# R205B.net
KiCad netlist of a schematic drawn in EAGLE
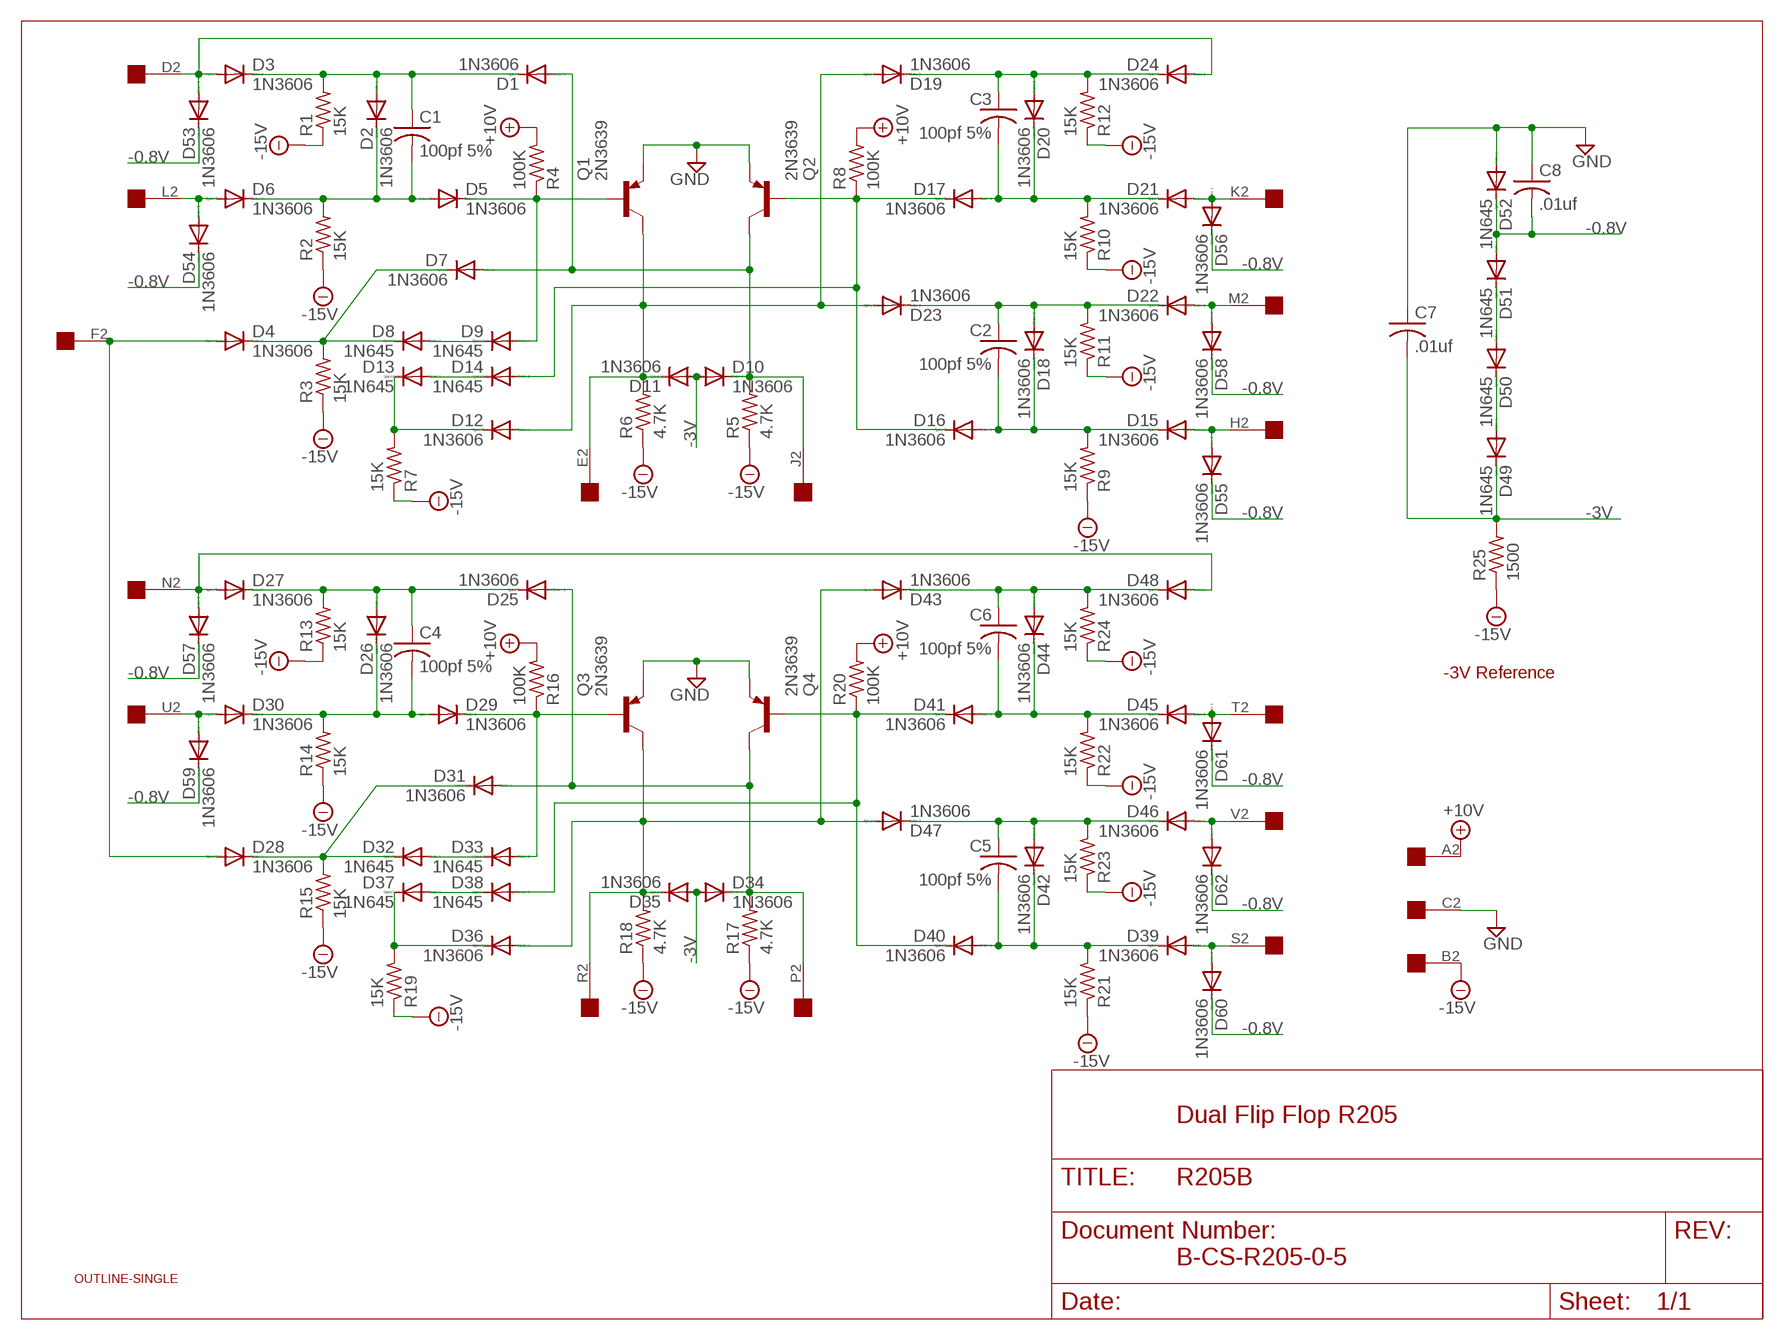
[diagram p0: schematic, sheet 1]

(export (version "E")
  (design (tool "Eeschema 10.0.6"))
  (components
    (comp (ref "C1")
      (value "100pf 5%")
      (footprint "eagle-import:C050-025X075")
      (libsource (lib "eagle-import") (part "C-US050-025X075"))
    )
    (comp (ref "C2")
      (value "100pf 5%")
      (footprint "eagle-import:C050-025X075")
      (libsource (lib "eagle-import") (part "C-US050-025X075"))
    )
    (comp (ref "C3")
      (value "100pf 5%")
      (footprint "eagle-import:C050-025X075")
      (libsource (lib "eagle-import") (part "C-US050-025X075"))
    )
    (comp (ref "C4")
      (value "100pf 5%")
      (footprint "eagle-import:C050-025X075")
      (libsource (lib "eagle-import") (part "C-US050-025X075"))
    )
    (comp (ref "C5")
      (value "100pf 5%")
      (footprint "eagle-import:C050-025X075")
      (libsource (lib "eagle-import") (part "C-US050-025X075"))
    )
    (comp (ref "C6")
      (value "100pf 5%")
      (footprint "eagle-import:C050-025X075")
      (libsource (lib "eagle-import") (part "C-US050-025X075"))
    )
    (comp (ref "C7")
      (value ".01uf")
      (footprint "eagle-import:C050-025X075")
      (libsource (lib "eagle-import") (part "C-US050-025X075"))
    )
    (comp (ref "C8")
      (value ".01uf")
      (footprint "eagle-import:C050-025X075")
      (libsource (lib "eagle-import") (part "C-US050-025X075"))
    )
    (comp (ref "D1")
      (value "1N3606")
      (footprint "eagle-import:DO35-10")
      (libsource (lib "eagle-import") (part "1N4148DO35-10"))
    )
    (comp (ref "D2")
      (value "1N3606")
      (footprint "eagle-import:DO35-10")
      (libsource (lib "eagle-import") (part "1N4148DO35-10"))
    )
    (comp (ref "D3")
      (value "1N3606")
      (footprint "eagle-import:DO35-10")
      (libsource (lib "eagle-import") (part "1N4148DO35-10"))
    )
    (comp (ref "D4")
      (value "1N3606")
      (footprint "eagle-import:DO35-10")
      (libsource (lib "eagle-import") (part "1N4148DO35-10"))
    )
    (comp (ref "D5")
      (value "1N3606")
      (footprint "eagle-import:DO35-10")
      (libsource (lib "eagle-import") (part "1N4148DO35-10"))
    )
    (comp (ref "D6")
      (value "1N3606")
      (footprint "eagle-import:DO35-10")
      (libsource (lib "eagle-import") (part "1N4148DO35-10"))
    )
    (comp (ref "D7")
      (value "1N3606")
      (footprint "eagle-import:DO35-10")
      (libsource (lib "eagle-import") (part "1N4148DO35-10"))
    )
    (comp (ref "D8")
      (value "1N645")
      (footprint "eagle-import:DO35-10")
      (libsource (lib "eagle-import") (part "1N4148DO35-10"))
    )
    (comp (ref "D9")
      (value "1N645")
      (footprint "eagle-import:DO35-10")
      (libsource (lib "eagle-import") (part "1N4148DO35-10"))
    )
    (comp (ref "D10")
      (value "1N3606")
      (footprint "eagle-import:DO35-10")
      (libsource (lib "eagle-import") (part "1N4148DO35-10"))
    )
    (comp (ref "D11")
      (value "1N3606")
      (footprint "eagle-import:DO35-10")
      (libsource (lib "eagle-import") (part "1N4148DO35-10"))
    )
    (comp (ref "D12")
      (value "1N3606")
      (footprint "eagle-import:DO35-10")
      (libsource (lib "eagle-import") (part "1N4148DO35-10"))
    )
    (comp (ref "D13")
      (value "1N645")
      (footprint "eagle-import:DO35-10")
      (libsource (lib "eagle-import") (part "1N4148DO35-10"))
    )
    (comp (ref "D14")
      (value "1N645")
      (footprint "eagle-import:DO35-10")
      (libsource (lib "eagle-import") (part "1N4148DO35-10"))
    )
    (comp (ref "D15")
      (value "1N3606")
      (footprint "eagle-import:DO35-10")
      (libsource (lib "eagle-import") (part "1N4148DO35-10"))
    )
    (comp (ref "D16")
      (value "1N3606")
      (footprint "eagle-import:DO35-10")
      (libsource (lib "eagle-import") (part "1N4148DO35-10"))
    )
    (comp (ref "D17")
      (value "1N3606")
      (footprint "eagle-import:DO35-10")
      (libsource (lib "eagle-import") (part "1N4148DO35-10"))
    )
    (comp (ref "D18")
      (value "1N3606")
      (footprint "eagle-import:DO35-10")
      (libsource (lib "eagle-import") (part "1N4148DO35-10"))
    )
    (comp (ref "D19")
      (value "1N3606")
      (footprint "eagle-import:DO35-10")
      (libsource (lib "eagle-import") (part "1N4148DO35-10"))
    )
    (comp (ref "D20")
      (value "1N3606")
      (footprint "eagle-import:DO35-10")
      (libsource (lib "eagle-import") (part "1N4148DO35-10"))
    )
    (comp (ref "D21")
      (value "1N3606")
      (footprint "eagle-import:DO35-10")
      (libsource (lib "eagle-import") (part "1N4148DO35-10"))
    )
    (comp (ref "D22")
      (value "1N3606")
      (footprint "eagle-import:DO35-10")
      (libsource (lib "eagle-import") (part "1N4148DO35-10"))
    )
    (comp (ref "D23")
      (value "1N3606")
      (footprint "eagle-import:DO35-10")
      (libsource (lib "eagle-import") (part "1N4148DO35-10"))
    )
    (comp (ref "D24")
      (value "1N3606")
      (footprint "eagle-import:DO35-10")
      (libsource (lib "eagle-import") (part "1N4148DO35-10"))
    )
    (comp (ref "D25")
      (value "1N3606")
      (footprint "eagle-import:DO35-10")
      (libsource (lib "eagle-import") (part "1N4148DO35-10"))
    )
    (comp (ref "D26")
      (value "1N3606")
      (footprint "eagle-import:DO35-10")
      (libsource (lib "eagle-import") (part "1N4148DO35-10"))
    )
    (comp (ref "D27")
      (value "1N3606")
      (footprint "eagle-import:DO35-10")
      (libsource (lib "eagle-import") (part "1N4148DO35-10"))
    )
    (comp (ref "D28")
      (value "1N3606")
      (footprint "eagle-import:DO35-10")
      (libsource (lib "eagle-import") (part "1N4148DO35-10"))
    )
    (comp (ref "D29")
      (value "1N3606")
      (footprint "eagle-import:DO35-10")
      (libsource (lib "eagle-import") (part "1N4148DO35-10"))
    )
    (comp (ref "D30")
      (value "1N3606")
      (footprint "eagle-import:DO35-10")
      (libsource (lib "eagle-import") (part "1N4148DO35-10"))
    )
    (comp (ref "D31")
      (value "1N3606")
      (footprint "eagle-import:DO35-10")
      (libsource (lib "eagle-import") (part "1N4148DO35-10"))
    )
    (comp (ref "D32")
      (value "1N645")
      (footprint "eagle-import:DO35-10")
      (libsource (lib "eagle-import") (part "1N4148DO35-10"))
    )
    (comp (ref "D33")
      (value "1N645")
      (footprint "eagle-import:DO35-10")
      (libsource (lib "eagle-import") (part "1N4148DO35-10"))
    )
    (comp (ref "D34")
      (value "1N3606")
      (footprint "eagle-import:DO35-10")
      (libsource (lib "eagle-import") (part "1N4148DO35-10"))
    )
    (comp (ref "D35")
      (value "1N3606")
      (footprint "eagle-import:DO35-10")
      (libsource (lib "eagle-import") (part "1N4148DO35-10"))
    )
    (comp (ref "D36")
      (value "1N3606")
      (footprint "eagle-import:DO35-10")
      (libsource (lib "eagle-import") (part "1N4148DO35-10"))
    )
    (comp (ref "D37")
      (value "1N645")
      (footprint "eagle-import:DO35-10")
      (libsource (lib "eagle-import") (part "1N4148DO35-10"))
    )
    (comp (ref "D38")
      (value "1N645")
      (footprint "eagle-import:DO35-10")
      (libsource (lib "eagle-import") (part "1N4148DO35-10"))
    )
    (comp (ref "D39")
      (value "1N3606")
      (footprint "eagle-import:DO35-10")
      (libsource (lib "eagle-import") (part "1N4148DO35-10"))
    )
    (comp (ref "D40")
      (value "1N3606")
      (footprint "eagle-import:DO35-10")
      (libsource (lib "eagle-import") (part "1N4148DO35-10"))
    )
    (comp (ref "D41")
      (value "1N3606")
      (footprint "eagle-import:DO35-10")
      (libsource (lib "eagle-import") (part "1N4148DO35-10"))
    )
    (comp (ref "D42")
      (value "1N3606")
      (footprint "eagle-import:DO35-10")
      (libsource (lib "eagle-import") (part "1N4148DO35-10"))
    )
    (comp (ref "D43")
      (value "1N3606")
      (footprint "eagle-import:DO35-10")
      (libsource (lib "eagle-import") (part "1N4148DO35-10"))
    )
    (comp (ref "D44")
      (value "1N3606")
      (footprint "eagle-import:DO35-10")
      (libsource (lib "eagle-import") (part "1N4148DO35-10"))
    )
    (comp (ref "D45")
      (value "1N3606")
      (footprint "eagle-import:DO35-10")
      (libsource (lib "eagle-import") (part "1N4148DO35-10"))
    )
    (comp (ref "D46")
      (value "1N3606")
      (footprint "eagle-import:DO35-10")
      (libsource (lib "eagle-import") (part "1N4148DO35-10"))
    )
    (comp (ref "D47")
      (value "1N3606")
      (footprint "eagle-import:DO35-10")
      (libsource (lib "eagle-import") (part "1N4148DO35-10"))
    )
    (comp (ref "D48")
      (value "1N3606")
      (footprint "eagle-import:DO35-10")
      (libsource (lib "eagle-import") (part "1N4148DO35-10"))
    )
    (comp (ref "D49")
      (value "1N645")
      (footprint "eagle-import:DO35-10")
      (libsource (lib "eagle-import") (part "1N4148DO35-10"))
    )
    (comp (ref "D50")
      (value "1N645")
      (footprint "eagle-import:DO35-10")
      (libsource (lib "eagle-import") (part "1N4148DO35-10"))
    )
    (comp (ref "D51")
      (value "1N645")
      (footprint "eagle-import:DO35-10")
      (libsource (lib "eagle-import") (part "1N4148DO35-10"))
    )
    (comp (ref "D52")
      (value "1N645")
      (footprint "eagle-import:DO35-10")
      (libsource (lib "eagle-import") (part "1N4148DO35-10"))
    )
    (comp (ref "D53")
      (value "1N3606")
      (footprint "eagle-import:DO35-10")
      (libsource (lib "eagle-import") (part "1N4148DO35-10"))
    )
    (comp (ref "D54")
      (value "1N3606")
      (footprint "eagle-import:DO35-10")
      (libsource (lib "eagle-import") (part "1N4148DO35-10"))
    )
    (comp (ref "D55")
      (value "1N3606")
      (footprint "eagle-import:DO35-10")
      (libsource (lib "eagle-import") (part "1N4148DO35-10"))
    )
    (comp (ref "D56")
      (value "1N3606")
      (footprint "eagle-import:DO35-10")
      (libsource (lib "eagle-import") (part "1N4148DO35-10"))
    )
    (comp (ref "D57")
      (value "1N3606")
      (footprint "eagle-import:DO35-10")
      (libsource (lib "eagle-import") (part "1N4148DO35-10"))
    )
    (comp (ref "D58")
      (value "1N3606")
      (footprint "eagle-import:DO35-10")
      (libsource (lib "eagle-import") (part "1N4148DO35-10"))
    )
    (comp (ref "D59")
      (value "1N3606")
      (footprint "eagle-import:DO35-10")
      (libsource (lib "eagle-import") (part "1N4148DO35-10"))
    )
    (comp (ref "D60")
      (value "1N3606")
      (footprint "eagle-import:DO35-10")
      (libsource (lib "eagle-import") (part "1N4148DO35-10"))
    )
    (comp (ref "D61")
      (value "1N3606")
      (footprint "eagle-import:DO35-10")
      (libsource (lib "eagle-import") (part "1N4148DO35-10"))
    )
    (comp (ref "D62")
      (value "1N3606")
      (footprint "eagle-import:DO35-10")
      (libsource (lib "eagle-import") (part "1N4148DO35-10"))
    )
    (comp (ref "Q1")
      (value "2N3639")
      (footprint "eagle-import:TO39")
      (libsource (lib "eagle-import") (part "2N3637"))
    )
    (comp (ref "Q2")
      (value "2N3639")
      (footprint "eagle-import:TO39")
      (libsource (lib "eagle-import") (part "2N3637"))
    )
    (comp (ref "Q3")
      (value "2N3639")
      (footprint "eagle-import:TO39")
      (libsource (lib "eagle-import") (part "2N3637"))
    )
    (comp (ref "Q4")
      (value "2N3639")
      (footprint "eagle-import:TO39")
      (libsource (lib "eagle-import") (part "2N3637"))
    )
    (comp (ref "R1")
      (value "15K")
      (footprint "eagle-import:0207_10")
      (libsource (lib "eagle-import") (part "R-US_0207/10"))
    )
    (comp (ref "R2")
      (value "15K")
      (footprint "eagle-import:0207_10")
      (libsource (lib "eagle-import") (part "R-US_0207/10"))
    )
    (comp (ref "R3")
      (value "15K")
      (footprint "eagle-import:0207_10")
      (libsource (lib "eagle-import") (part "R-US_0207/10"))
    )
    (comp (ref "R4")
      (value "100K")
      (footprint "eagle-import:0207_10")
      (libsource (lib "eagle-import") (part "R-US_0207/10"))
    )
    (comp (ref "R5")
      (value "4.7K")
      (footprint "eagle-import:0207_10")
      (libsource (lib "eagle-import") (part "R-US_0207/10"))
    )
    (comp (ref "R6")
      (value "4.7K")
      (footprint "eagle-import:0207_10")
      (libsource (lib "eagle-import") (part "R-US_0207/10"))
    )
    (comp (ref "R7")
      (value "15K")
      (footprint "eagle-import:0207_10")
      (libsource (lib "eagle-import") (part "R-US_0207/10"))
    )
    (comp (ref "R8")
      (value "100K")
      (footprint "eagle-import:0207_10")
      (libsource (lib "eagle-import") (part "R-US_0207/10"))
    )
    (comp (ref "R9")
      (value "15K")
      (footprint "eagle-import:0207_10")
      (libsource (lib "eagle-import") (part "R-US_0207/10"))
    )
    (comp (ref "R10")
      (value "15K")
      (footprint "eagle-import:0207_10")
      (libsource (lib "eagle-import") (part "R-US_0207/10"))
    )
    (comp (ref "R11")
      (value "15K")
      (footprint "eagle-import:0207_10")
      (libsource (lib "eagle-import") (part "R-US_0207/10"))
    )
    (comp (ref "R12")
      (value "15K")
      (footprint "eagle-import:0207_10")
      (libsource (lib "eagle-import") (part "R-US_0207/10"))
    )
    (comp (ref "R13")
      (value "15K")
      (footprint "eagle-import:0207_10")
      (libsource (lib "eagle-import") (part "R-US_0207/10"))
    )
    (comp (ref "R14")
      (value "15K")
      (footprint "eagle-import:0207_10")
      (libsource (lib "eagle-import") (part "R-US_0207/10"))
    )
    (comp (ref "R15")
      (value "15K")
      (footprint "eagle-import:0207_10")
      (libsource (lib "eagle-import") (part "R-US_0207/10"))
    )
    (comp (ref "R16")
      (value "100K")
      (footprint "eagle-import:0207_10")
      (libsource (lib "eagle-import") (part "R-US_0207/10"))
    )
    (comp (ref "R17")
      (value "4.7K")
      (footprint "eagle-import:0207_10")
      (libsource (lib "eagle-import") (part "R-US_0207/10"))
    )
    (comp (ref "R18")
      (value "4.7K")
      (footprint "eagle-import:0207_10")
      (libsource (lib "eagle-import") (part "R-US_0207/10"))
    )
    (comp (ref "R19")
      (value "15K")
      (footprint "eagle-import:0207_10")
      (libsource (lib "eagle-import") (part "R-US_0207/10"))
    )
    (comp (ref "R20")
      (value "100K")
      (footprint "eagle-import:0207_10")
      (libsource (lib "eagle-import") (part "R-US_0207/10"))
    )
    (comp (ref "R21")
      (value "15K")
      (footprint "eagle-import:0207_10")
      (libsource (lib "eagle-import") (part "R-US_0207/10"))
    )
    (comp (ref "R22")
      (value "15K")
      (footprint "eagle-import:0207_10")
      (libsource (lib "eagle-import") (part "R-US_0207/10"))
    )
    (comp (ref "R23")
      (value "15K")
      (footprint "eagle-import:0207_10")
      (libsource (lib "eagle-import") (part "R-US_0207/10"))
    )
    (comp (ref "R24")
      (value "15K")
      (footprint "eagle-import:0207_10")
      (libsource (lib "eagle-import") (part "R-US_0207/10"))
    )
    (comp (ref "R25")
      (value "1500")
      (footprint "eagle-import:0207_10")
      (libsource (lib "eagle-import") (part "R-US_0207/10"))
    )
    (comp (ref "U$1")
      (value "OUTLINE-SINGLE")
      (footprint "eagle-import:SINGLE")
      (libsource (lib "eagle-import") (part "OUTLINE-SINGLE"))
    )
    (comp (ref "U$2")
      (value "EDGE-1")
      (footprint "eagle-import:EDGE-CON1")
      (libsource (lib "eagle-import") (part "EDGE-1"))
    )
  )
  (nets
    (net (code "1") (name "+10V") (class "Default")
      (node (ref "R16") (pin "2") (pinfunction "2_2") (pintype "passive"))
      (node (ref "R20") (pin "2") (pinfunction "2_2") (pintype "passive"))
      (node (ref "R4") (pin "2") (pinfunction "2_2") (pintype "passive"))
      (node (ref "R8") (pin "2") (pinfunction "2_2") (pintype "passive"))
      (node (ref "U$2") (pin "A2") (pinfunction "1_A2") (pintype "bidirectional"))
    )
    (net (code "2") (name "-15V") (class "Default")
      (node (ref "R1") (pin "1") (pinfunction "1_1") (pintype "passive"))
      (node (ref "R10") (pin "1") (pinfunction "1_1") (pintype "passive"))
      (node (ref "R11") (pin "1") (pinfunction "1_1") (pintype "passive"))
      (node (ref "R12") (pin "1") (pinfunction "1_1") (pintype "passive"))
      (node (ref "R13") (pin "1") (pinfunction "1_1") (pintype "passive"))
      (node (ref "R14") (pin "1") (pinfunction "1_1") (pintype "passive"))
      (node (ref "R15") (pin "1") (pinfunction "1_1") (pintype "passive"))
      (node (ref "R17") (pin "1") (pinfunction "1_1") (pintype "passive"))
      (node (ref "R18") (pin "1") (pinfunction "1_1") (pintype "passive"))
      (node (ref "R19") (pin "1") (pinfunction "1_1") (pintype "passive"))
      (node (ref "R2") (pin "1") (pinfunction "1_1") (pintype "passive"))
      (node (ref "R21") (pin "1") (pinfunction "1_1") (pintype "passive"))
      (node (ref "R22") (pin "1") (pinfunction "1_1") (pintype "passive"))
      (node (ref "R23") (pin "1") (pinfunction "1_1") (pintype "passive"))
      (node (ref "R24") (pin "1") (pinfunction "1_1") (pintype "passive"))
      (node (ref "R25") (pin "1") (pinfunction "1_1") (pintype "passive"))
      (node (ref "R3") (pin "1") (pinfunction "1_1") (pintype "passive"))
      (node (ref "R5") (pin "1") (pinfunction "1_1") (pintype "passive"))
      (node (ref "R6") (pin "1") (pinfunction "1_1") (pintype "passive"))
      (node (ref "R7") (pin "1") (pinfunction "1_1") (pintype "passive"))
      (node (ref "R9") (pin "1") (pinfunction "1_1") (pintype "passive"))
      (node (ref "U$2") (pin "B2") (pinfunction "1_B2") (pintype "bidirectional"))
    )
    (net (code "3") (name "/-0.8V") (class "Default")
      (node (ref "C8") (pin "2") (pinfunction "2_2") (pintype "passive"))
      (node (ref "D51") (pin "A") (pinfunction "A_A") (pintype "passive"))
      (node (ref "D52") (pin "C") (pinfunction "C_C") (pintype "passive"))
      (node (ref "D53") (pin "C") (pinfunction "C_C") (pintype "passive"))
      (node (ref "D54") (pin "C") (pinfunction "C_C") (pintype "passive"))
      (node (ref "D55") (pin "C") (pinfunction "C_C") (pintype "passive"))
      (node (ref "D56") (pin "C") (pinfunction "C_C") (pintype "passive"))
      (node (ref "D57") (pin "C") (pinfunction "C_C") (pintype "passive"))
      (node (ref "D58") (pin "C") (pinfunction "C_C") (pintype "passive"))
      (node (ref "D59") (pin "C") (pinfunction "C_C") (pintype "passive"))
      (node (ref "D60") (pin "C") (pinfunction "C_C") (pintype "passive"))
      (node (ref "D61") (pin "C") (pinfunction "C_C") (pintype "passive"))
      (node (ref "D62") (pin "C") (pinfunction "C_C") (pintype "passive"))
    )
    (net (code "4") (name "/-3V") (class "Default")
      (node (ref "C7") (pin "2") (pinfunction "2_2") (pintype "passive"))
      (node (ref "D10") (pin "A") (pinfunction "A_A") (pintype "passive"))
      (node (ref "D11") (pin "A") (pinfunction "A_A") (pintype "passive"))
      (node (ref "D34") (pin "A") (pinfunction "A_A") (pintype "passive"))
      (node (ref "D35") (pin "A") (pinfunction "A_A") (pintype "passive"))
      (node (ref "D49") (pin "C") (pinfunction "C_C") (pintype "passive"))
      (node (ref "R25") (pin "2") (pinfunction "2_2") (pintype "passive"))
    )
    (net (code "5") (name "GND") (class "Default")
      (node (ref "C7") (pin "1") (pinfunction "1_1") (pintype "passive"))
      (node (ref "C8") (pin "1") (pinfunction "1_1") (pintype "passive"))
      (node (ref "D52") (pin "A") (pinfunction "A_A") (pintype "passive"))
      (node (ref "Q1") (pin "1") (pinfunction "E_1") (pintype "passive"))
      (node (ref "Q2") (pin "1") (pinfunction "E_1") (pintype "passive"))
      (node (ref "Q3") (pin "1") (pinfunction "E_1") (pintype "passive"))
      (node (ref "Q4") (pin "1") (pinfunction "E_1") (pintype "passive"))
      (node (ref "U$2") (pin "C2") (pinfunction "1_C2") (pintype "bidirectional"))
    )
    (net (code "6") (name "Net-(C1-Pad1)") (class "Default")
      (node (ref "C1") (pin "1") (pinfunction "1_1") (pintype "passive"))
      (node (ref "D1") (pin "C") (pinfunction "C_C") (pintype "passive"))
      (node (ref "D2") (pin "A") (pinfunction "A_A") (pintype "passive"))
      (node (ref "D3") (pin "C") (pinfunction "C_C") (pintype "passive"))
      (node (ref "R1") (pin "2") (pinfunction "2_2") (pintype "passive"))
    )
    (net (code "7") (name "Net-(C1-Pad2)") (class "Default")
      (node (ref "C1") (pin "2") (pinfunction "2_2") (pintype "passive"))
      (node (ref "D2") (pin "C") (pinfunction "C_C") (pintype "passive"))
      (node (ref "D5") (pin "A") (pinfunction "A_A") (pintype "passive"))
      (node (ref "D6") (pin "C") (pinfunction "C_C") (pintype "passive"))
      (node (ref "R2") (pin "2") (pinfunction "2_2") (pintype "passive"))
    )
    (net (code "8") (name "Net-(C2-Pad1)") (class "Default")
      (node (ref "C2") (pin "1") (pinfunction "1_1") (pintype "passive"))
      (node (ref "D18") (pin "A") (pinfunction "A_A") (pintype "passive"))
      (node (ref "D22") (pin "C") (pinfunction "C_C") (pintype "passive"))
      (node (ref "D23") (pin "C") (pinfunction "C_C") (pintype "passive"))
      (node (ref "R11") (pin "2") (pinfunction "2_2") (pintype "passive"))
    )
    (net (code "9") (name "Net-(C2-Pad2)") (class "Default")
      (node (ref "C2") (pin "2") (pinfunction "2_2") (pintype "passive"))
      (node (ref "D15") (pin "C") (pinfunction "C_C") (pintype "passive"))
      (node (ref "D16") (pin "A") (pinfunction "A_A") (pintype "passive"))
      (node (ref "D18") (pin "C") (pinfunction "C_C") (pintype "passive"))
      (node (ref "R9") (pin "2") (pinfunction "2_2") (pintype "passive"))
    )
    (net (code "10") (name "Net-(C3-Pad1)") (class "Default")
      (node (ref "C3") (pin "1") (pinfunction "1_1") (pintype "passive"))
      (node (ref "D19") (pin "C") (pinfunction "C_C") (pintype "passive"))
      (node (ref "D20") (pin "A") (pinfunction "A_A") (pintype "passive"))
      (node (ref "D24") (pin "C") (pinfunction "C_C") (pintype "passive"))
      (node (ref "R12") (pin "2") (pinfunction "2_2") (pintype "passive"))
    )
    (net (code "11") (name "Net-(C3-Pad2)") (class "Default")
      (node (ref "C3") (pin "2") (pinfunction "2_2") (pintype "passive"))
      (node (ref "D17") (pin "A") (pinfunction "A_A") (pintype "passive"))
      (node (ref "D20") (pin "C") (pinfunction "C_C") (pintype "passive"))
      (node (ref "D21") (pin "C") (pinfunction "C_C") (pintype "passive"))
      (node (ref "R10") (pin "2") (pinfunction "2_2") (pintype "passive"))
    )
    (net (code "12") (name "Net-(C4-Pad1)") (class "Default")
      (node (ref "C4") (pin "1") (pinfunction "1_1") (pintype "passive"))
      (node (ref "D25") (pin "C") (pinfunction "C_C") (pintype "passive"))
      (node (ref "D26") (pin "A") (pinfunction "A_A") (pintype "passive"))
      (node (ref "D27") (pin "C") (pinfunction "C_C") (pintype "passive"))
      (node (ref "R13") (pin "2") (pinfunction "2_2") (pintype "passive"))
    )
    (net (code "13") (name "Net-(C4-Pad2)") (class "Default")
      (node (ref "C4") (pin "2") (pinfunction "2_2") (pintype "passive"))
      (node (ref "D26") (pin "C") (pinfunction "C_C") (pintype "passive"))
      (node (ref "D29") (pin "A") (pinfunction "A_A") (pintype "passive"))
      (node (ref "D30") (pin "C") (pinfunction "C_C") (pintype "passive"))
      (node (ref "R14") (pin "2") (pinfunction "2_2") (pintype "passive"))
    )
    (net (code "14") (name "Net-(C5-Pad1)") (class "Default")
      (node (ref "C5") (pin "1") (pinfunction "1_1") (pintype "passive"))
      (node (ref "D42") (pin "A") (pinfunction "A_A") (pintype "passive"))
      (node (ref "D46") (pin "C") (pinfunction "C_C") (pintype "passive"))
      (node (ref "D47") (pin "C") (pinfunction "C_C") (pintype "passive"))
      (node (ref "R23") (pin "2") (pinfunction "2_2") (pintype "passive"))
    )
    (net (code "15") (name "Net-(C5-Pad2)") (class "Default")
      (node (ref "C5") (pin "2") (pinfunction "2_2") (pintype "passive"))
      (node (ref "D39") (pin "C") (pinfunction "C_C") (pintype "passive"))
      (node (ref "D40") (pin "A") (pinfunction "A_A") (pintype "passive"))
      (node (ref "D42") (pin "C") (pinfunction "C_C") (pintype "passive"))
      (node (ref "R21") (pin "2") (pinfunction "2_2") (pintype "passive"))
    )
    (net (code "16") (name "Net-(C6-Pad1)") (class "Default")
      (node (ref "C6") (pin "1") (pinfunction "1_1") (pintype "passive"))
      (node (ref "D43") (pin "C") (pinfunction "C_C") (pintype "passive"))
      (node (ref "D44") (pin "A") (pinfunction "A_A") (pintype "passive"))
      (node (ref "D48") (pin "C") (pinfunction "C_C") (pintype "passive"))
      (node (ref "R24") (pin "2") (pinfunction "2_2") (pintype "passive"))
    )
    (net (code "17") (name "Net-(C6-Pad2)") (class "Default")
      (node (ref "C6") (pin "2") (pinfunction "2_2") (pintype "passive"))
      (node (ref "D41") (pin "A") (pinfunction "A_A") (pintype "passive"))
      (node (ref "D44") (pin "C") (pinfunction "C_C") (pintype "passive"))
      (node (ref "D45") (pin "C") (pinfunction "C_C") (pintype "passive"))
      (node (ref "R22") (pin "2") (pinfunction "2_2") (pintype "passive"))
    )
    (net (code "18") (name "Net-(D4-PadC)") (class "Default")
      (node (ref "D4") (pin "C") (pinfunction "C_C") (pintype "passive"))
      (node (ref "D7") (pin "C") (pinfunction "C_C") (pintype "passive"))
      (node (ref "D8") (pin "C") (pinfunction "C_C") (pintype "passive"))
      (node (ref "R3") (pin "2") (pinfunction "2_2") (pintype "passive"))
    )
    (net (code "19") (name "Net-(D8-PadA)") (class "Default")
      (node (ref "D8") (pin "A") (pinfunction "A_A") (pintype "passive"))
      (node (ref "D9") (pin "C") (pinfunction "C_C") (pintype "passive"))
    )
    (net (code "20") (name "Net-(D12-PadC)") (class "Default")
      (node (ref "D12") (pin "C") (pinfunction "C_C") (pintype "passive"))
      (node (ref "D13") (pin "C") (pinfunction "C_C") (pintype "passive"))
      (node (ref "R7") (pin "2") (pinfunction "2_2") (pintype "passive"))
    )
    (net (code "21") (name "Net-(D13-PadA)") (class "Default")
      (node (ref "D13") (pin "A") (pinfunction "A_A") (pintype "passive"))
      (node (ref "D14") (pin "C") (pinfunction "C_C") (pintype "passive"))
    )
    (net (code "22") (name "Net-(D28-PadC)") (class "Default")
      (node (ref "D28") (pin "C") (pinfunction "C_C") (pintype "passive"))
      (node (ref "D31") (pin "C") (pinfunction "C_C") (pintype "passive"))
      (node (ref "D32") (pin "C") (pinfunction "C_C") (pintype "passive"))
      (node (ref "R15") (pin "2") (pinfunction "2_2") (pintype "passive"))
    )
    (net (code "23") (name "Net-(D32-PadA)") (class "Default")
      (node (ref "D32") (pin "A") (pinfunction "A_A") (pintype "passive"))
      (node (ref "D33") (pin "C") (pinfunction "C_C") (pintype "passive"))
    )
    (net (code "24") (name "Net-(D36-PadC)") (class "Default")
      (node (ref "D36") (pin "C") (pinfunction "C_C") (pintype "passive"))
      (node (ref "D37") (pin "C") (pinfunction "C_C") (pintype "passive"))
      (node (ref "R19") (pin "2") (pinfunction "2_2") (pintype "passive"))
    )
    (net (code "25") (name "Net-(D37-PadA)") (class "Default")
      (node (ref "D37") (pin "A") (pinfunction "A_A") (pintype "passive"))
      (node (ref "D38") (pin "C") (pinfunction "C_C") (pintype "passive"))
    )
    (net (code "26") (name "Net-(D49-PadA)") (class "Default")
      (node (ref "D49") (pin "A") (pinfunction "A_A") (pintype "passive"))
      (node (ref "D50") (pin "C") (pinfunction "C_C") (pintype "passive"))
    )
    (net (code "27") (name "Net-(D50-PadA)") (class "Default")
      (node (ref "D50") (pin "A") (pinfunction "A_A") (pintype "passive"))
      (node (ref "D51") (pin "C") (pinfunction "C_C") (pintype "passive"))
    )
    (net (code "28") (name "Net-(Q1-B)") (class "Default")
      (node (ref "D5") (pin "C") (pinfunction "C_C") (pintype "passive"))
      (node (ref "D9") (pin "A") (pinfunction "A_A") (pintype "passive"))
      (node (ref "Q1") (pin "2") (pinfunction "B_2") (pintype "passive"))
      (node (ref "R4") (pin "1") (pinfunction "1_1") (pintype "passive"))
    )
    (net (code "29") (name "Net-(Q1-C)") (class "Default")
      (node (ref "D11") (pin "C") (pinfunction "C_C") (pintype "passive"))
      (node (ref "D12") (pin "A") (pinfunction "A_A") (pintype "passive"))
      (node (ref "D19") (pin "A") (pinfunction "A_A") (pintype "passive"))
      (node (ref "D23") (pin "A") (pinfunction "A_A") (pintype "passive"))
      (node (ref "Q1") (pin "3") (pinfunction "C_3") (pintype "passive"))
      (node (ref "R6") (pin "2") (pinfunction "2_2") (pintype "passive"))
      (node (ref "U$2") (pin "E2") (pinfunction "1_E2") (pintype "bidirectional"))
    )
    (net (code "30") (name "Net-(Q2-B)") (class "Default")
      (node (ref "D14") (pin "A") (pinfunction "A_A") (pintype "passive"))
      (node (ref "D16") (pin "C") (pinfunction "C_C") (pintype "passive"))
      (node (ref "D17") (pin "C") (pinfunction "C_C") (pintype "passive"))
      (node (ref "Q2") (pin "2") (pinfunction "B_2") (pintype "passive"))
      (node (ref "R8") (pin "1") (pinfunction "1_1") (pintype "passive"))
    )
    (net (code "31") (name "Net-(Q2-C)") (class "Default")
      (node (ref "D1") (pin "A") (pinfunction "A_A") (pintype "passive"))
      (node (ref "D10") (pin "C") (pinfunction "C_C") (pintype "passive"))
      (node (ref "D7") (pin "A") (pinfunction "A_A") (pintype "passive"))
      (node (ref "Q2") (pin "3") (pinfunction "C_3") (pintype "passive"))
      (node (ref "R5") (pin "2") (pinfunction "2_2") (pintype "passive"))
      (node (ref "U$2") (pin "J2") (pinfunction "1_J2") (pintype "bidirectional"))
    )
    (net (code "32") (name "Net-(Q3-B)") (class "Default")
      (node (ref "D29") (pin "C") (pinfunction "C_C") (pintype "passive"))
      (node (ref "D33") (pin "A") (pinfunction "A_A") (pintype "passive"))
      (node (ref "Q3") (pin "2") (pinfunction "B_2") (pintype "passive"))
      (node (ref "R16") (pin "1") (pinfunction "1_1") (pintype "passive"))
    )
    (net (code "33") (name "Net-(Q3-C)") (class "Default")
      (node (ref "D35") (pin "C") (pinfunction "C_C") (pintype "passive"))
      (node (ref "D36") (pin "A") (pinfunction "A_A") (pintype "passive"))
      (node (ref "D43") (pin "A") (pinfunction "A_A") (pintype "passive"))
      (node (ref "D47") (pin "A") (pinfunction "A_A") (pintype "passive"))
      (node (ref "Q3") (pin "3") (pinfunction "C_3") (pintype "passive"))
      (node (ref "R18") (pin "2") (pinfunction "2_2") (pintype "passive"))
      (node (ref "U$2") (pin "R2") (pinfunction "1_R2") (pintype "bidirectional"))
    )
    (net (code "34") (name "Net-(Q4-B)") (class "Default")
      (node (ref "D38") (pin "A") (pinfunction "A_A") (pintype "passive"))
      (node (ref "D40") (pin "C") (pinfunction "C_C") (pintype "passive"))
      (node (ref "D41") (pin "C") (pinfunction "C_C") (pintype "passive"))
      (node (ref "Q4") (pin "2") (pinfunction "B_2") (pintype "passive"))
      (node (ref "R20") (pin "1") (pinfunction "1_1") (pintype "passive"))
    )
    (net (code "35") (name "Net-(Q4-C)") (class "Default")
      (node (ref "D25") (pin "A") (pinfunction "A_A") (pintype "passive"))
      (node (ref "D31") (pin "A") (pinfunction "A_A") (pintype "passive"))
      (node (ref "D34") (pin "C") (pinfunction "C_C") (pintype "passive"))
      (node (ref "Q4") (pin "3") (pinfunction "C_3") (pintype "passive"))
      (node (ref "R17") (pin "2") (pinfunction "2_2") (pintype "passive"))
      (node (ref "U$2") (pin "P2") (pinfunction "1_P2") (pintype "bidirectional"))
    )
    (net (code "36") (name "Net-(U$2D-1)") (class "Default")
      (node (ref "D24") (pin "A") (pinfunction "A_A") (pintype "passive"))
      (node (ref "D3") (pin "A") (pinfunction "A_A") (pintype "passive"))
      (node (ref "D53") (pin "A") (pinfunction "A_A") (pintype "passive"))
      (node (ref "U$2") (pin "D2") (pinfunction "1_D2") (pintype "bidirectional"))
    )
    (net (code "37") (name "Net-(U$2F-1)") (class "Default")
      (node (ref "D28") (pin "A") (pinfunction "A_A") (pintype "passive"))
      (node (ref "D4") (pin "A") (pinfunction "A_A") (pintype "passive"))
      (node (ref "U$2") (pin "F2") (pinfunction "1_F2") (pintype "bidirectional"))
    )
    (net (code "38") (name "Net-(U$2G-1)") (class "Default")
      (node (ref "D15") (pin "A") (pinfunction "A_A") (pintype "passive"))
      (node (ref "D55") (pin "A") (pinfunction "A_A") (pintype "passive"))
      (node (ref "U$2") (pin "H2") (pinfunction "1_H2") (pintype "bidirectional"))
    )
    (net (code "39") (name "Net-(U$2I-1)") (class "Default")
      (node (ref "D21") (pin "A") (pinfunction "A_A") (pintype "passive"))
      (node (ref "D56") (pin "A") (pinfunction "A_A") (pintype "passive"))
      (node (ref "U$2") (pin "K2") (pinfunction "1_K2") (pintype "bidirectional"))
    )
    (net (code "40") (name "Net-(U$2J-1)") (class "Default")
      (node (ref "D54") (pin "A") (pinfunction "A_A") (pintype "passive"))
      (node (ref "D6") (pin "A") (pinfunction "A_A") (pintype "passive"))
      (node (ref "U$2") (pin "L2") (pinfunction "1_L2") (pintype "bidirectional"))
    )
    (net (code "41") (name "Net-(U$2K-1)") (class "Default")
      (node (ref "D22") (pin "A") (pinfunction "A_A") (pintype "passive"))
      (node (ref "D58") (pin "A") (pinfunction "A_A") (pintype "passive"))
      (node (ref "U$2") (pin "M2") (pinfunction "1_M2") (pintype "bidirectional"))
    )
    (net (code "42") (name "Net-(U$2L-1)") (class "Default")
      (node (ref "D27") (pin "A") (pinfunction "A_A") (pintype "passive"))
      (node (ref "D48") (pin "A") (pinfunction "A_A") (pintype "passive"))
      (node (ref "D57") (pin "A") (pinfunction "A_A") (pintype "passive"))
      (node (ref "U$2") (pin "N2") (pinfunction "1_N2") (pintype "bidirectional"))
    )
    (net (code "43") (name "Net-(U$2O-1)") (class "Default")
      (node (ref "D39") (pin "A") (pinfunction "A_A") (pintype "passive"))
      (node (ref "D60") (pin "A") (pinfunction "A_A") (pintype "passive"))
      (node (ref "U$2") (pin "S2") (pinfunction "1_S2") (pintype "bidirectional"))
    )
    (net (code "44") (name "Net-(U$2P-1)") (class "Default")
      (node (ref "D45") (pin "A") (pinfunction "A_A") (pintype "passive"))
      (node (ref "D61") (pin "A") (pinfunction "A_A") (pintype "passive"))
      (node (ref "U$2") (pin "T2") (pinfunction "1_T2") (pintype "bidirectional"))
    )
    (net (code "45") (name "Net-(U$2Q-1)") (class "Default")
      (node (ref "D30") (pin "A") (pinfunction "A_A") (pintype "passive"))
      (node (ref "D59") (pin "A") (pinfunction "A_A") (pintype "passive"))
      (node (ref "U$2") (pin "U2") (pinfunction "1_U2") (pintype "bidirectional"))
    )
    (net (code "46") (name "Net-(U$2R-1)") (class "Default")
      (node (ref "D46") (pin "A") (pinfunction "A_A") (pintype "passive"))
      (node (ref "D62") (pin "A") (pinfunction "A_A") (pintype "passive"))
      (node (ref "U$2") (pin "V2") (pinfunction "1_V2") (pintype "bidirectional"))
    )
  )
)
